# device.net
KiCad netlist of a schematic drawn in EAGLE
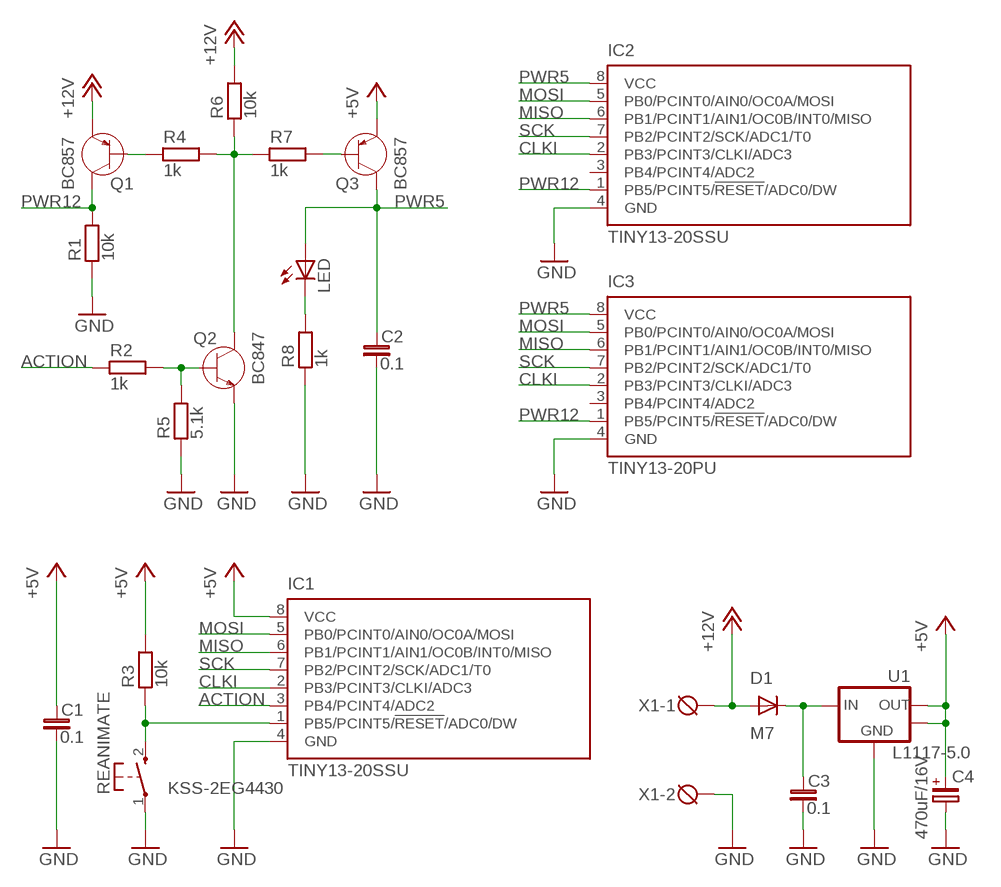
[diagram p0: schematic, sheet 1]

(export (version "E")
  (design (tool "Eeschema 10.0.6"))
  (components
    (comp (ref "C1")
      (value "0.1")
      (footprint "eagle-import:C0805")
      (libsource (lib "eagle-import") (part "C_0805"))
    )
    (comp (ref "C2")
      (value "0.1")
      (footprint "eagle-import:C0805")
      (libsource (lib "eagle-import") (part "C_0805"))
    )
    (comp (ref "C3")
      (value "0.1")
      (footprint "eagle-import:C0805")
      (libsource (lib "eagle-import") (part "C_0805"))
    )
    (comp (ref "C4")
      (value "470uF/16V")
      (footprint "eagle-import:C175TMP-0810")
      (libsource (lib "eagle-import") (part "CP_BC175TMP-0810"))
    )
    (comp (ref "D1")
      (value "M7")
      (footprint "eagle-import:DO214AC")
      (libsource (lib "eagle-import") (part "DIODE-DO214AC"))
    )
    (comp (ref "IC1")
      (value "TINY13-20SSU")
      (footprint "eagle-import:8S1")
      (libsource (lib "eagle-import") (part "TINY13SSU-20"))
    )
    (comp (ref "IC2")
      (value "TINY13-20SSU")
      (footprint "eagle-import:8S1")
      (libsource (lib "eagle-import") (part "TINY13SSU-20"))
    )
    (comp (ref "IC3")
      (value "TINY13-20PU")
      (footprint "eagle-import:DIL08")
      (libsource (lib "eagle-import") (part "TINY13PU-20"))
    )
    (comp (ref "LED")
      (value "LEDCHIPLED_0805")
      (footprint "eagle-import:CHIPLED_0805")
      (libsource (lib "eagle-import") (part "LEDCHIPLED_0805"))
    )
    (comp (ref "Q1")
      (value "BC857")
      (footprint "eagle-import:SOT23")
      (libsource (lib "eagle-import") (part "PNP-SOT23"))
    )
    (comp (ref "Q2")
      (value "BC847")
      (footprint "eagle-import:SOT23")
      (libsource (lib "eagle-import") (part "NPN-SOT23"))
    )
    (comp (ref "Q3")
      (value "BC857")
      (footprint "eagle-import:SOT23")
      (libsource (lib "eagle-import") (part "PNP-SOT23"))
    )
    (comp (ref "R1")
      (value "10k")
      (footprint "eagle-import:R0805")
      (libsource (lib "eagle-import") (part "R_0805"))
    )
    (comp (ref "R2")
      (value "1k")
      (footprint "eagle-import:R0805")
      (libsource (lib "eagle-import") (part "R_0805"))
    )
    (comp (ref "R3")
      (value "10k")
      (footprint "eagle-import:R0805")
      (libsource (lib "eagle-import") (part "R_0805"))
    )
    (comp (ref "R4")
      (value "1k")
      (footprint "eagle-import:R0805")
      (libsource (lib "eagle-import") (part "R_0805"))
    )
    (comp (ref "R5")
      (value "5.1k")
      (footprint "eagle-import:R0805")
      (libsource (lib "eagle-import") (part "R_0805"))
    )
    (comp (ref "R6")
      (value "10k")
      (footprint "eagle-import:R0805")
      (libsource (lib "eagle-import") (part "R_0805"))
    )
    (comp (ref "R7")
      (value "1k")
      (footprint "eagle-import:R0805")
      (libsource (lib "eagle-import") (part "R_0805"))
    )
    (comp (ref "R8")
      (value "1k")
      (footprint "eagle-import:R0805")
      (libsource (lib "eagle-import") (part "R_0805"))
    )
    (comp (ref "REANIMATE")
      (value "KSS-2EG4430")
      (footprint "eagle-import:KSS-2EG4430")
      (libsource (lib "eagle-import") (part "KSS-2EG4430"))
    )
    (comp (ref "U1")
      (value "L1117-5.0")
      (footprint "eagle-import:SOT223")
      (libsource (lib "eagle-import") (part "LM1117-3.3"))
    )
    (comp (ref "X1")
      (value "DG3XX-02-5.0")
      (footprint "eagle-import:DG306-5.0-02P")
      (libsource (lib "eagle-import") (part "DG3XX-02-5.0"))
    )
  )
  (nets
    (net (code "1") (name "+5V") (class "Default")
      (node (ref "C1") (pin "1") (pinfunction "1_1") (pintype "passive"))
      (node (ref "C4") (pin "+") (pinfunction "+_+") (pintype "passive"))
      (node (ref "IC1") (pin "8") (pinfunction "VCC_8") (pintype "power_in"))
      (node (ref "Q3") (pin "2") (pinfunction "E_2") (pintype "passive"))
      (node (ref "R3") (pin "2") (pinfunction "2_2") (pintype "passive"))
      (node (ref "U1") (pin "2") (pinfunction "OUT_2") (pintype "output"))
      (node (ref "U1") (pin "4") (pinfunction "MASS_4") (pintype "passive"))
    )
    (net (code "2") (name "+12V") (class "Default")
      (node (ref "D1") (pin "A") (pinfunction "A_A") (pintype "passive"))
      (node (ref "Q1") (pin "2") (pinfunction "E_2") (pintype "passive"))
      (node (ref "R6") (pin "2") (pinfunction "2_2") (pintype "passive"))
      (node (ref "X1") (pin "1") (pinfunction "KL_1") (pintype "passive"))
    )
    (net (code "3") (name "/ACTION") (class "Default")
      (node (ref "IC1") (pin "3") (pinfunction "PB4/PCINT4/ADC2_3") (pintype "bidirectional"))
      (node (ref "R2") (pin "1") (pinfunction "1_1") (pintype "passive"))
    )
    (net (code "4") (name "/CLKI") (class "Default")
      (node (ref "IC1") (pin "2") (pinfunction "PB3/PCINT3/CLKI/ADC3_2") (pintype "bidirectional"))
      (node (ref "IC2") (pin "2") (pinfunction "PB3/PCINT3/CLKI/ADC3_2") (pintype "bidirectional"))
      (node (ref "IC3") (pin "2") (pinfunction "PB3/PCINT3/CLKI/ADC3_2") (pintype "bidirectional"))
    )
    (net (code "5") (name "/MISO") (class "Default")
      (node (ref "IC1") (pin "6") (pinfunction "PB1/PCINT1/AIN1/OC0B/INT0/MISO_6") (pintype "bidirectional"))
      (node (ref "IC2") (pin "6") (pinfunction "PB1/PCINT1/AIN1/OC0B/INT0/MISO_6") (pintype "bidirectional"))
      (node (ref "IC3") (pin "6") (pinfunction "PB1/PCINT1/AIN1/OC0B/INT0/MISO_6") (pintype "bidirectional"))
    )
    (net (code "6") (name "/MOSI") (class "Default")
      (node (ref "IC1") (pin "5") (pinfunction "PB0/PCINT0/AIN0/OC0A/MOSI_5") (pintype "bidirectional"))
      (node (ref "IC2") (pin "5") (pinfunction "PB0/PCINT0/AIN0/OC0A/MOSI_5") (pintype "bidirectional"))
      (node (ref "IC3") (pin "5") (pinfunction "PB0/PCINT0/AIN0/OC0A/MOSI_5") (pintype "bidirectional"))
    )
    (net (code "7") (name "/PWR5") (class "Default")
      (node (ref "C2") (pin "1") (pinfunction "1_1") (pintype "passive"))
      (node (ref "IC2") (pin "8") (pinfunction "VCC_8") (pintype "power_in"))
      (node (ref "IC3") (pin "8") (pinfunction "VCC_8") (pintype "power_in"))
      (node (ref "LED") (pin "A") (pinfunction "A_A") (pintype "passive"))
      (node (ref "Q3") (pin "3") (pinfunction "C_3") (pintype "passive"))
    )
    (net (code "8") (name "/PWR12") (class "Default")
      (node (ref "IC2") (pin "1") (pinfunction "PB5/PCINT5/~{RESET}/ADC0/DW_1") (pintype "bidirectional"))
      (node (ref "IC3") (pin "1") (pinfunction "PB5/PCINT5/~{RESET}/ADC0/DW_1") (pintype "bidirectional"))
      (node (ref "Q1") (pin "3") (pinfunction "C_3") (pintype "passive"))
      (node (ref "R1") (pin "2") (pinfunction "2_2") (pintype "passive"))
    )
    (net (code "9") (name "/SCK") (class "Default")
      (node (ref "IC1") (pin "7") (pinfunction "PB2/PCINT2/SCK/ADC1/T0_7") (pintype "bidirectional"))
      (node (ref "IC2") (pin "7") (pinfunction "PB2/PCINT2/SCK/ADC1/T0_7") (pintype "bidirectional"))
      (node (ref "IC3") (pin "7") (pinfunction "PB2/PCINT2/SCK/ADC1/T0_7") (pintype "bidirectional"))
    )
    (net (code "10") (name "GND") (class "Default")
      (node (ref "C1") (pin "2") (pinfunction "2_2") (pintype "passive"))
      (node (ref "C2") (pin "2") (pinfunction "2_2") (pintype "passive"))
      (node (ref "C3") (pin "2") (pinfunction "2_2") (pintype "passive"))
      (node (ref "C4") (pin "-") (pinfunction "-_-") (pintype "passive"))
      (node (ref "IC1") (pin "4") (pinfunction "GND_4") (pintype "power_in"))
      (node (ref "IC2") (pin "4") (pinfunction "GND_4") (pintype "power_in"))
      (node (ref "IC3") (pin "4") (pinfunction "GND_4") (pintype "power_in"))
      (node (ref "Q2") (pin "2") (pinfunction "E_2") (pintype "passive"))
      (node (ref "R1") (pin "1") (pinfunction "1_1") (pintype "passive"))
      (node (ref "R5") (pin "1") (pinfunction "1_1") (pintype "passive"))
      (node (ref "R8") (pin "1") (pinfunction "1_1") (pintype "passive"))
      (node (ref "REANIMATE") (pin "1") (pinfunction "P_1") (pintype "passive"))
      (node (ref "U1") (pin "1") (pinfunction "GND_1") (pintype "power_in"))
      (node (ref "X1") (pin "2") (pinfunction "KL_2") (pintype "passive"))
    )
    (net (code "11") (name "Net-(IC1-PB5{slash}PCINT5{slash}~{RESET}{slash}ADC0{slash}DW)") (class "Default")
      (node (ref "IC1") (pin "1") (pinfunction "PB5/PCINT5/~{RESET}/ADC0/DW_1") (pintype "bidirectional"))
      (node (ref "R3") (pin "1") (pinfunction "1_1") (pintype "passive"))
      (node (ref "REANIMATE") (pin "2") (pinfunction "S_2") (pintype "passive"))
    )
    (net (code "12") (name "Net-(LED-PadC)") (class "Default")
      (node (ref "LED") (pin "C") (pinfunction "C_C") (pintype "passive"))
      (node (ref "R8") (pin "2") (pinfunction "2_2") (pintype "passive"))
    )
    (net (code "13") (name "Net-(Q1-B)") (class "Default")
      (node (ref "Q1") (pin "1") (pinfunction "B_1") (pintype "passive"))
      (node (ref "R4") (pin "1") (pinfunction "1_1") (pintype "passive"))
    )
    (net (code "14") (name "Net-(Q2-B)") (class "Default")
      (node (ref "Q2") (pin "1") (pinfunction "B_1") (pintype "passive"))
      (node (ref "R2") (pin "2") (pinfunction "2_2") (pintype "passive"))
      (node (ref "R5") (pin "2") (pinfunction "2_2") (pintype "passive"))
    )
    (net (code "15") (name "Net-(Q2-C)") (class "Default")
      (node (ref "Q2") (pin "3") (pinfunction "C_3") (pintype "passive"))
      (node (ref "R4") (pin "2") (pinfunction "2_2") (pintype "passive"))
      (node (ref "R6") (pin "1") (pinfunction "1_1") (pintype "passive"))
      (node (ref "R7") (pin "1") (pinfunction "1_1") (pintype "passive"))
    )
    (net (code "16") (name "Net-(Q3-B)") (class "Default")
      (node (ref "Q3") (pin "1") (pinfunction "B_1") (pintype "passive"))
      (node (ref "R7") (pin "2") (pinfunction "2_2") (pintype "passive"))
    )
    (net (code "17") (name "Net-(U1-IN)") (class "Default")
      (node (ref "C3") (pin "1") (pinfunction "1_1") (pintype "passive"))
      (node (ref "D1") (pin "C") (pinfunction "C_C") (pintype "passive"))
      (node (ref "U1") (pin "3") (pinfunction "IN_3") (pintype "power_in"))
    )
    (net (code "18") (name "unconnected-(IC2-PB4{slash}PCINT4{slash}ADC2-Pad3)") (class "Default")
      (node (ref "IC2") (pin "3") (pinfunction "PB4/PCINT4/ADC2_3") (pintype "bidirectional"))
    )
    (net (code "19") (name "unconnected-(IC3-PB4{slash}PCINT4{slash}ADC2-Pad3)") (class "Default")
      (node (ref "IC3") (pin "3") (pinfunction "PB4/PCINT4/ADC2_3") (pintype "bidirectional"))
    )
  )
)
